# VGA.net
KiCad netlist of a schematic drawn in Altium Designer
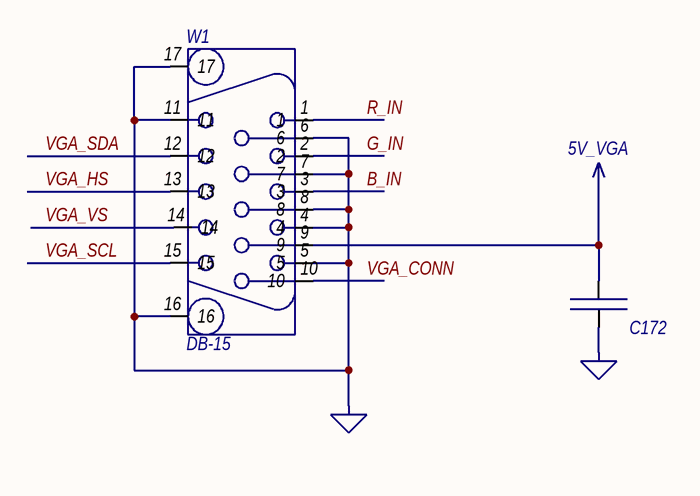
[diagram p0: VGA.SchDoc]

(export (version "E")
  (design (tool "Eeschema 10.0.6"))
  (components
    (comp (ref "C172")
      (value "*")
      (footprint "lab_7_footprints:Cap_tantal_D")
      (libsource (lib "31_lib") (part "Capacitor"))
    )
    (comp (ref "W1")
      (value "DB-15")
      (footprint "31_lib:VGA")
      (libsource (lib "31_lib") (part "VGA_connector"))
    )
  )
  (nets
    (net (code "1") (name "/B_IN") (class "Default")
      (node (ref "W1") (pin "3") (pinfunction "3_3") (pintype "passive"))
    )
    (net (code "2") (name "/G_IN") (class "Default")
      (node (ref "W1") (pin "2") (pinfunction "2_2") (pintype "passive"))
    )
    (net (code "3") (name "/R_IN") (class "Default")
      (node (ref "W1") (pin "1") (pinfunction "1_1") (pintype "passive"))
    )
    (net (code "4") (name "/VGA_CONN") (class "Default")
      (node (ref "W1") (pin "10") (pinfunction "10_10") (pintype "passive"))
    )
    (net (code "5") (name "/VGA_HS") (class "Default")
      (node (ref "W1") (pin "13") (pinfunction "13_13") (pintype "passive"))
    )
    (net (code "6") (name "/VGA_SCL") (class "Default")
      (node (ref "W1") (pin "15") (pinfunction "15_15") (pintype "passive"))
    )
    (net (code "7") (name "/VGA_SDA") (class "Default")
      (node (ref "W1") (pin "12") (pinfunction "12_12") (pintype "passive"))
    )
    (net (code "8") (name "/VGA_VS") (class "Default")
      (node (ref "W1") (pin "14") (pinfunction "14_14") (pintype "passive"))
    )
    (net (code "9") (name "5V_VGA") (class "Default")
      (node (ref "C172") (pin "2") (pinfunction "2_2") (pintype "passive"))
      (node (ref "W1") (pin "9") (pinfunction "9_9") (pintype "passive"))
    )
    (net (code "10") (name "GND") (class "Default")
      (node (ref "C172") (pin "1") (pinfunction "1_1") (pintype "passive"))
      (node (ref "W1") (pin "11") (pinfunction "11_11") (pintype "passive"))
      (node (ref "W1") (pin "16") (pinfunction "16_16") (pintype "passive"))
      (node (ref "W1") (pin "17") (pinfunction "17_17") (pintype "passive"))
      (node (ref "W1") (pin "4") (pinfunction "4_4") (pintype "passive"))
      (node (ref "W1") (pin "5") (pinfunction "5_5") (pintype "passive"))
      (node (ref "W1") (pin "6") (pinfunction "6_6") (pintype "passive"))
      (node (ref "W1") (pin "7") (pinfunction "7_7") (pintype "passive"))
      (node (ref "W1") (pin "8") (pinfunction "8_8") (pintype "passive"))
    )
  )
)
